# 02_ZYNQ_POWER.net
KiCad netlist of a schematic drawn in Altium Designer
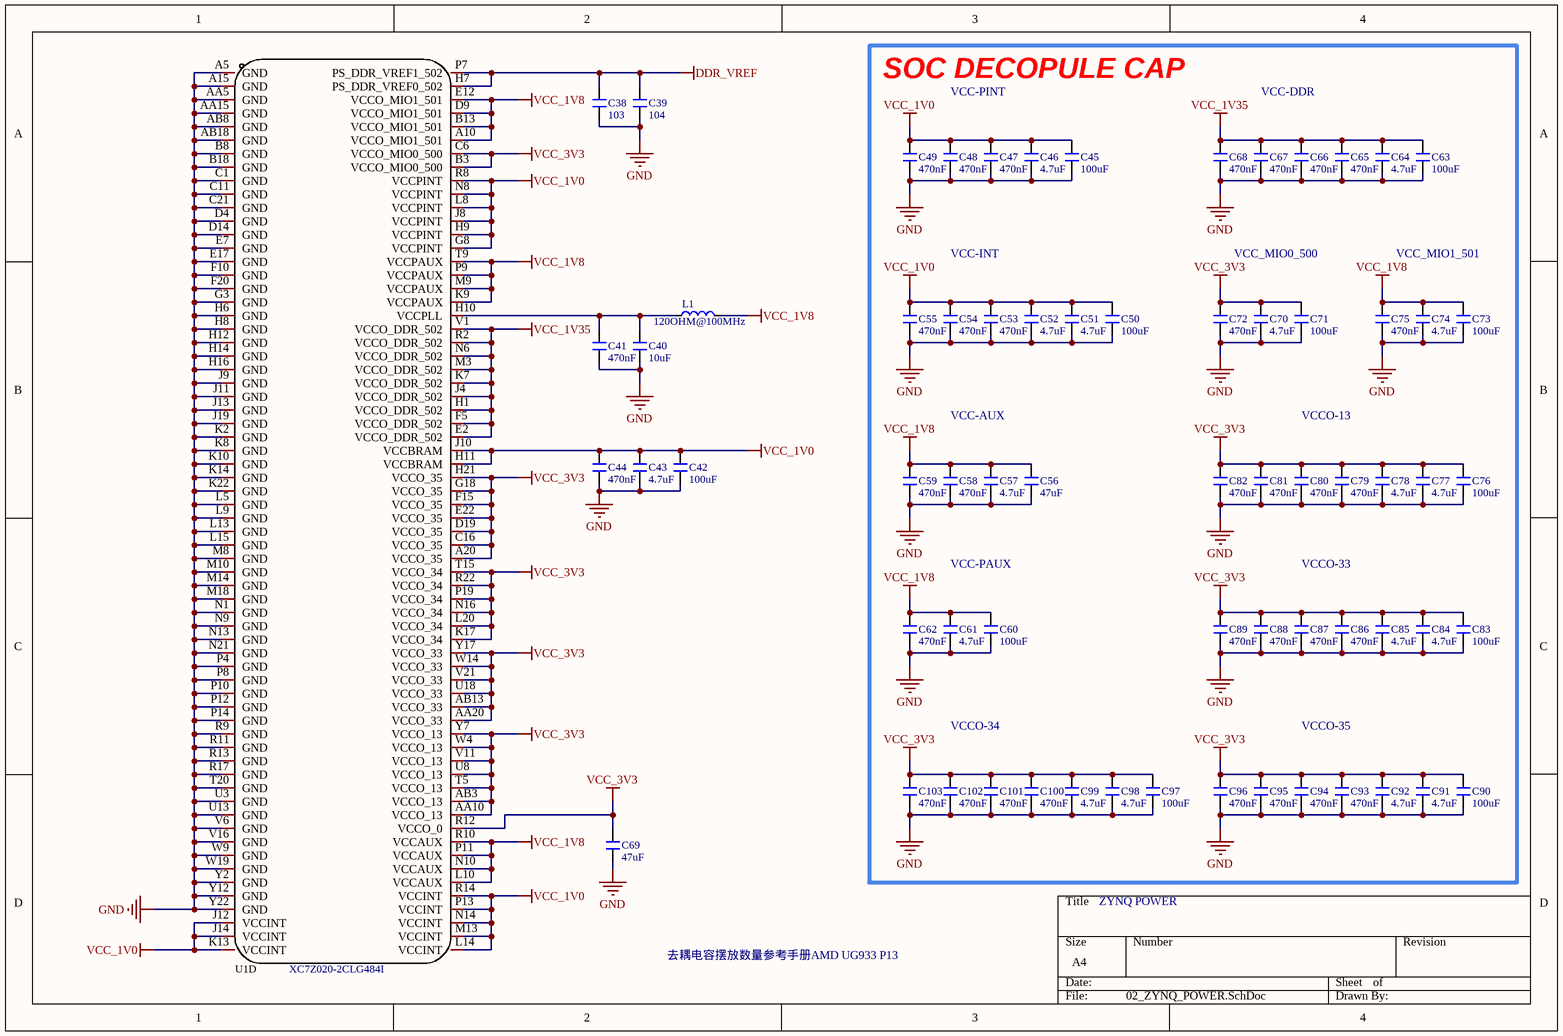
[diagram p0: 02_ZYNQ_POWER.SchDoc]

(export (version "E")
  (design (tool "Eeschema 10.0.6"))
  (components
    (comp (ref "C38")
      (value "103")
      (footprint "C 0402")
      (description "无极性贴片电容")
      (fields (field (name "版权归属") "源创客"))
      (libsource (lib "STM32MP157核心板封装库V1.2") (part "C"))
    )
    (comp (ref "C39")
      (value "104")
      (footprint "C 0402")
      (description "无极性贴片电容")
      (fields (field (name "版权归属") "源创客"))
      (libsource (lib "STM32MP157核心板封装库V1.2") (part "C"))
    )
    (comp (ref "C40")
      (value "10uF")
      (footprint "C 0402")
      (description "无极性贴片电容")
      (fields (field (name "版权归属") "源创客"))
      (libsource (lib "STM32MP157核心板封装库V1.2") (part "C"))
    )
    (comp (ref "C41")
      (value "470nF")
      (footprint "C 0402")
      (description "无极性贴片电容")
      (fields (field (name "版权归属") "源创客"))
      (libsource (lib "STM32MP157核心板封装库V1.2") (part "C"))
    )
    (comp (ref "C42")
      (value "100uF")
      (footprint "C 0805")
      (description "无极性贴片电容")
      (fields (field (name "版权归属") "源创客"))
      (libsource (lib "STM32MP157核心板封装库V1.2") (part "C"))
    )
    (comp (ref "C43")
      (value "4.7uF")
      (footprint "C 0402")
      (description "无极性贴片电容")
      (fields (field (name "版权归属") "源创客"))
      (libsource (lib "STM32MP157核心板封装库V1.2") (part "C"))
    )
    (comp (ref "C44")
      (value "470nF")
      (footprint "C 0402")
      (description "无极性贴片电容")
      (fields (field (name "版权归属") "源创客"))
      (libsource (lib "STM32MP157核心板封装库V1.2") (part "C"))
    )
    (comp (ref "C45")
      (value "100uF")
      (footprint "C 0805")
      (description "无极性贴片电容")
      (fields (field (name "版权归属") "源创客"))
      (libsource (lib "STM32MP157核心板封装库V1.2") (part "C"))
    )
    (comp (ref "C46")
      (value "4.7uF")
      (footprint "C 0402")
      (description "无极性贴片电容")
      (fields (field (name "版权归属") "源创客"))
      (libsource (lib "STM32MP157核心板封装库V1.2") (part "C"))
    )
    (comp (ref "C47")
      (value "470nF")
      (footprint "C 0402")
      (description "无极性贴片电容")
      (fields (field (name "版权归属") "源创客"))
      (libsource (lib "STM32MP157核心板封装库V1.2") (part "C"))
    )
    (comp (ref "C48")
      (value "470nF")
      (footprint "C 0402")
      (description "无极性贴片电容")
      (fields (field (name "版权归属") "源创客"))
      (libsource (lib "STM32MP157核心板封装库V1.2") (part "C"))
    )
    (comp (ref "C49")
      (value "470nF")
      (footprint "C 0402")
      (description "无极性贴片电容")
      (fields (field (name "版权归属") "源创客"))
      (libsource (lib "STM32MP157核心板封装库V1.2") (part "C"))
    )
    (comp (ref "C50")
      (value "100uF")
      (footprint "C 0805")
      (description "无极性贴片电容")
      (fields (field (name "版权归属") "源创客"))
      (libsource (lib "STM32MP157核心板封装库V1.2") (part "C"))
    )
    (comp (ref "C51")
      (value "4.7uF")
      (footprint "C 0402")
      (description "无极性贴片电容")
      (fields (field (name "版权归属") "源创客"))
      (libsource (lib "STM32MP157核心板封装库V1.2") (part "C"))
    )
    (comp (ref "C52")
      (value "4.7uF")
      (footprint "C 0402")
      (description "无极性贴片电容")
      (fields (field (name "版权归属") "源创客"))
      (libsource (lib "STM32MP157核心板封装库V1.2") (part "C"))
    )
    (comp (ref "C53")
      (value "470nF")
      (footprint "C 0402")
      (description "无极性贴片电容")
      (fields (field (name "版权归属") "源创客"))
      (libsource (lib "STM32MP157核心板封装库V1.2") (part "C"))
    )
    (comp (ref "C54")
      (value "470nF")
      (footprint "C 0402")
      (description "无极性贴片电容")
      (fields (field (name "版权归属") "源创客"))
      (libsource (lib "STM32MP157核心板封装库V1.2") (part "C"))
    )
    (comp (ref "C55")
      (value "470nF")
      (footprint "C 0402")
      (description "无极性贴片电容")
      (fields (field (name "版权归属") "源创客"))
      (libsource (lib "STM32MP157核心板封装库V1.2") (part "C"))
    )
    (comp (ref "C56")
      (value "47uF")
      (footprint "C 0805")
      (description "无极性贴片电容")
      (fields (field (name "版权归属") "源创客"))
      (libsource (lib "STM32MP157核心板封装库V1.2") (part "C"))
    )
    (comp (ref "C57")
      (value "4.7uF")
      (footprint "C 0402")
      (description "无极性贴片电容")
      (fields (field (name "版权归属") "源创客"))
      (libsource (lib "STM32MP157核心板封装库V1.2") (part "C"))
    )
    (comp (ref "C58")
      (value "470nF")
      (footprint "C 0402")
      (description "无极性贴片电容")
      (fields (field (name "版权归属") "源创客"))
      (libsource (lib "STM32MP157核心板封装库V1.2") (part "C"))
    )
    (comp (ref "C59")
      (value "470nF")
      (footprint "C 0402")
      (description "无极性贴片电容")
      (fields (field (name "版权归属") "源创客"))
      (libsource (lib "STM32MP157核心板封装库V1.2") (part "C"))
    )
    (comp (ref "C60")
      (value "100uF")
      (footprint "C 0805")
      (description "无极性贴片电容")
      (fields (field (name "版权归属") "源创客"))
      (libsource (lib "STM32MP157核心板封装库V1.2") (part "C"))
    )
    (comp (ref "C61")
      (value "4.7uF")
      (footprint "C 0402")
      (description "无极性贴片电容")
      (fields (field (name "版权归属") "源创客"))
      (libsource (lib "STM32MP157核心板封装库V1.2") (part "C"))
    )
    (comp (ref "C62")
      (value "470nF")
      (footprint "C 0402")
      (description "无极性贴片电容")
      (fields (field (name "版权归属") "源创客"))
      (libsource (lib "STM32MP157核心板封装库V1.2") (part "C"))
    )
    (comp (ref "C63")
      (value "100uF")
      (footprint "C 0805")
      (description "无极性贴片电容")
      (fields (field (name "版权归属") "源创客"))
      (libsource (lib "STM32MP157核心板封装库V1.2") (part "C"))
    )
    (comp (ref "C64")
      (value "4.7uF")
      (footprint "C 0402")
      (description "无极性贴片电容")
      (fields (field (name "版权归属") "源创客"))
      (libsource (lib "STM32MP157核心板封装库V1.2") (part "C"))
    )
    (comp (ref "C65")
      (value "470nF")
      (footprint "C 0402")
      (description "无极性贴片电容")
      (fields (field (name "版权归属") "源创客"))
      (libsource (lib "STM32MP157核心板封装库V1.2") (part "C"))
    )
    (comp (ref "C66")
      (value "470nF")
      (footprint "C 0402")
      (description "无极性贴片电容")
      (fields (field (name "版权归属") "源创客"))
      (libsource (lib "STM32MP157核心板封装库V1.2") (part "C"))
    )
    (comp (ref "C67")
      (value "470nF")
      (footprint "C 0402")
      (description "无极性贴片电容")
      (fields (field (name "版权归属") "源创客"))
      (libsource (lib "STM32MP157核心板封装库V1.2") (part "C"))
    )
    (comp (ref "C68")
      (value "470nF")
      (footprint "C 0402")
      (description "无极性贴片电容")
      (fields (field (name "版权归属") "源创客"))
      (libsource (lib "STM32MP157核心板封装库V1.2") (part "C"))
    )
    (comp (ref "C69")
      (value "47uF")
      (footprint "C 0805")
      (description "无极性贴片电容")
      (fields (field (name "版权归属") "源创客"))
      (libsource (lib "STM32MP157核心板封装库V1.2") (part "C"))
    )
    (comp (ref "C70")
      (value "4.7uF")
      (footprint "C 0402")
      (description "无极性贴片电容")
      (fields (field (name "版权归属") "源创客"))
      (libsource (lib "STM32MP157核心板封装库V1.2") (part "C"))
    )
    (comp (ref "C71")
      (value "100uF")
      (footprint "C 0805")
      (description "无极性贴片电容")
      (fields (field (name "版权归属") "源创客"))
      (libsource (lib "STM32MP157核心板封装库V1.2") (part "C"))
    )
    (comp (ref "C72")
      (value "470nF")
      (footprint "C 0402")
      (description "无极性贴片电容")
      (fields (field (name "版权归属") "源创客"))
      (libsource (lib "STM32MP157核心板封装库V1.2") (part "C"))
    )
    (comp (ref "C73")
      (value "100uF")
      (footprint "C 0805")
      (description "无极性贴片电容")
      (fields (field (name "版权归属") "源创客"))
      (libsource (lib "STM32MP157核心板封装库V1.2") (part "C"))
    )
    (comp (ref "C74")
      (value "4.7uF")
      (footprint "C 0402")
      (description "无极性贴片电容")
      (fields (field (name "版权归属") "源创客"))
      (libsource (lib "STM32MP157核心板封装库V1.2") (part "C"))
    )
    (comp (ref "C75")
      (value "470nF")
      (footprint "C 0402")
      (description "无极性贴片电容")
      (fields (field (name "版权归属") "源创客"))
      (libsource (lib "STM32MP157核心板封装库V1.2") (part "C"))
    )
    (comp (ref "C76")
      (value "100uF")
      (footprint "C 0805")
      (description "无极性贴片电容")
      (fields (field (name "版权归属") "源创客"))
      (libsource (lib "STM32MP157核心板封装库V1.2") (part "C"))
    )
    (comp (ref "C77")
      (value "4.7uF")
      (footprint "C 0402")
      (description "无极性贴片电容")
      (fields (field (name "版权归属") "源创客"))
      (libsource (lib "STM32MP157核心板封装库V1.2") (part "C"))
    )
    (comp (ref "C78")
      (value "4.7uF")
      (footprint "C 0402")
      (description "无极性贴片电容")
      (fields (field (name "版权归属") "源创客"))
      (libsource (lib "STM32MP157核心板封装库V1.2") (part "C"))
    )
    (comp (ref "C79")
      (value "470nF")
      (footprint "C 0402")
      (description "无极性贴片电容")
      (fields (field (name "版权归属") "源创客"))
      (libsource (lib "STM32MP157核心板封装库V1.2") (part "C"))
    )
    (comp (ref "C80")
      (value "470nF")
      (footprint "C 0402")
      (description "无极性贴片电容")
      (fields (field (name "版权归属") "源创客"))
      (libsource (lib "STM32MP157核心板封装库V1.2") (part "C"))
    )
    (comp (ref "C81")
      (value "470nF")
      (footprint "C 0402")
      (description "无极性贴片电容")
      (fields (field (name "版权归属") "源创客"))
      (libsource (lib "STM32MP157核心板封装库V1.2") (part "C"))
    )
    (comp (ref "C82")
      (value "470nF")
      (footprint "C 0402")
      (description "无极性贴片电容")
      (fields (field (name "版权归属") "源创客"))
      (libsource (lib "STM32MP157核心板封装库V1.2") (part "C"))
    )
    (comp (ref "C83")
      (value "100uF")
      (footprint "C 0805")
      (description "无极性贴片电容")
      (fields (field (name "版权归属") "源创客"))
      (libsource (lib "STM32MP157核心板封装库V1.2") (part "C"))
    )
    (comp (ref "C84")
      (value "4.7uF")
      (footprint "C 0402")
      (description "无极性贴片电容")
      (fields (field (name "版权归属") "源创客"))
      (libsource (lib "STM32MP157核心板封装库V1.2") (part "C"))
    )
    (comp (ref "C85")
      (value "4.7uF")
      (footprint "C 0402")
      (description "无极性贴片电容")
      (fields (field (name "版权归属") "源创客"))
      (libsource (lib "STM32MP157核心板封装库V1.2") (part "C"))
    )
    (comp (ref "C86")
      (value "470nF")
      (footprint "C 0402")
      (description "无极性贴片电容")
      (fields (field (name "版权归属") "源创客"))
      (libsource (lib "STM32MP157核心板封装库V1.2") (part "C"))
    )
    (comp (ref "C87")
      (value "470nF")
      (footprint "C 0402")
      (description "无极性贴片电容")
      (fields (field (name "版权归属") "源创客"))
      (libsource (lib "STM32MP157核心板封装库V1.2") (part "C"))
    )
    (comp (ref "C88")
      (value "470nF")
      (footprint "C 0402")
      (description "无极性贴片电容")
      (fields (field (name "版权归属") "源创客"))
      (libsource (lib "STM32MP157核心板封装库V1.2") (part "C"))
    )
    (comp (ref "C89")
      (value "470nF")
      (footprint "C 0402")
      (description "无极性贴片电容")
      (fields (field (name "版权归属") "源创客"))
      (libsource (lib "STM32MP157核心板封装库V1.2") (part "C"))
    )
    (comp (ref "C90")
      (value "100uF")
      (footprint "C 0805")
      (description "无极性贴片电容")
      (fields (field (name "版权归属") "源创客"))
      (libsource (lib "STM32MP157核心板封装库V1.2") (part "C"))
    )
    (comp (ref "C91")
      (value "4.7uF")
      (footprint "C 0402")
      (description "无极性贴片电容")
      (fields (field (name "版权归属") "源创客"))
      (libsource (lib "STM32MP157核心板封装库V1.2") (part "C"))
    )
    (comp (ref "C92")
      (value "4.7uF")
      (footprint "C 0402")
      (description "无极性贴片电容")
      (fields (field (name "版权归属") "源创客"))
      (libsource (lib "STM32MP157核心板封装库V1.2") (part "C"))
    )
    (comp (ref "C93")
      (value "470nF")
      (footprint "C 0402")
      (description "无极性贴片电容")
      (fields (field (name "版权归属") "源创客"))
      (libsource (lib "STM32MP157核心板封装库V1.2") (part "C"))
    )
    (comp (ref "C94")
      (value "470nF")
      (footprint "C 0402")
      (description "无极性贴片电容")
      (fields (field (name "版权归属") "源创客"))
      (libsource (lib "STM32MP157核心板封装库V1.2") (part "C"))
    )
    (comp (ref "C95")
      (value "470nF")
      (footprint "C 0402")
      (description "无极性贴片电容")
      (fields (field (name "版权归属") "源创客"))
      (libsource (lib "STM32MP157核心板封装库V1.2") (part "C"))
    )
    (comp (ref "C96")
      (value "470nF")
      (footprint "C 0402")
      (description "无极性贴片电容")
      (fields (field (name "版权归属") "源创客"))
      (libsource (lib "STM32MP157核心板封装库V1.2") (part "C"))
    )
    (comp (ref "C97")
      (value "100uF")
      (footprint "C 0805")
      (description "无极性贴片电容")
      (fields (field (name "版权归属") "源创客"))
      (libsource (lib "STM32MP157核心板封装库V1.2") (part "C"))
    )
    (comp (ref "C98")
      (value "4.7uF")
      (footprint "C 0402")
      (description "无极性贴片电容")
      (fields (field (name "版权归属") "源创客"))
      (libsource (lib "STM32MP157核心板封装库V1.2") (part "C"))
    )
    (comp (ref "C99")
      (value "4.7uF")
      (footprint "C 0402")
      (description "无极性贴片电容")
      (fields (field (name "版权归属") "源创客"))
      (libsource (lib "STM32MP157核心板封装库V1.2") (part "C"))
    )
    (comp (ref "C100")
      (value "470nF")
      (footprint "C 0402")
      (description "无极性贴片电容")
      (fields (field (name "版权归属") "源创客"))
      (libsource (lib "STM32MP157核心板封装库V1.2") (part "C"))
    )
    (comp (ref "C101")
      (value "470nF")
      (footprint "C 0402")
      (description "无极性贴片电容")
      (fields (field (name "版权归属") "源创客"))
      (libsource (lib "STM32MP157核心板封装库V1.2") (part "C"))
    )
    (comp (ref "C102")
      (value "470nF")
      (footprint "C 0402")
      (description "无极性贴片电容")
      (fields (field (name "版权归属") "源创客"))
      (libsource (lib "STM32MP157核心板封装库V1.2") (part "C"))
    )
    (comp (ref "C103")
      (value "470nF")
      (footprint "C 0402")
      (description "无极性贴片电容")
      (fields (field (name "版权归属") "源创客"))
      (libsource (lib "STM32MP157核心板封装库V1.2") (part "C"))
    )
    (comp (ref "L1")
      (value "120OHM@100MHz")
      (footprint "L 0603")
      (description "小功率贴片电感磁珠")
      (fields (field (name "版权归属") "源创客"))
      (libsource (lib "STM32MP157核心板封装库V1.2") (part "L"))
    )
    (comp (ref "U1")
      (value "XC7Z020-2CLG484I")
      (footprint "FPBGA-484_L19.0-W19.0-R22-C22-P0.80-BL")
      (fields (field (name "MANUFACTURER") "XILINX(赛灵思)"))
      (libsource (lib "XC7Z020-2CLG484I1") (part "XC7Z020-2CLG484I"))
    )
  )
  (nets
    (net (code "1") (name "DDR_VREF") (class "Default")
      (node (ref "C38") (pin "2") (pinfunction "2_2") (pintype "passive"))
      (node (ref "C39") (pin "2") (pinfunction "2_2") (pintype "passive"))
      (node (ref "U1") (pin "H7") (pinfunction "PS_DDR_VREF0_502_H7") (pintype "passive"))
      (node (ref "U1") (pin "P7") (pinfunction "PS_DDR_VREF1_502_P7") (pintype "passive"))
    )
    (net (code "2") (name "GND") (class "Default")
      (node (ref "C100") (pin "1") (pinfunction "1_1") (pintype "passive"))
      (node (ref "C101") (pin "1") (pinfunction "1_1") (pintype "passive"))
      (node (ref "C102") (pin "1") (pinfunction "1_1") (pintype "passive"))
      (node (ref "C103") (pin "1") (pinfunction "1_1") (pintype "passive"))
      (node (ref "C38") (pin "1") (pinfunction "1_1") (pintype "passive"))
      (node (ref "C39") (pin "1") (pinfunction "1_1") (pintype "passive"))
      (node (ref "C40") (pin "1") (pinfunction "1_1") (pintype "passive"))
      (node (ref "C41") (pin "1") (pinfunction "1_1") (pintype "passive"))
      (node (ref "C42") (pin "1") (pinfunction "1_1") (pintype "passive"))
      (node (ref "C43") (pin "1") (pinfunction "1_1") (pintype "passive"))
      (node (ref "C44") (pin "1") (pinfunction "1_1") (pintype "passive"))
      (node (ref "C45") (pin "1") (pinfunction "1_1") (pintype "passive"))
      (node (ref "C46") (pin "1") (pinfunction "1_1") (pintype "passive"))
      (node (ref "C47") (pin "1") (pinfunction "1_1") (pintype "passive"))
      (node (ref "C48") (pin "1") (pinfunction "1_1") (pintype "passive"))
      (node (ref "C49") (pin "1") (pinfunction "1_1") (pintype "passive"))
      (node (ref "C50") (pin "1") (pinfunction "1_1") (pintype "passive"))
      (node (ref "C51") (pin "1") (pinfunction "1_1") (pintype "passive"))
      (node (ref "C52") (pin "1") (pinfunction "1_1") (pintype "passive"))
      (node (ref "C53") (pin "1") (pinfunction "1_1") (pintype "passive"))
      (node (ref "C54") (pin "1") (pinfunction "1_1") (pintype "passive"))
      (node (ref "C55") (pin "1") (pinfunction "1_1") (pintype "passive"))
      (node (ref "C56") (pin "1") (pinfunction "1_1") (pintype "passive"))
      (node (ref "C57") (pin "1") (pinfunction "1_1") (pintype "passive"))
      (node (ref "C58") (pin "1") (pinfunction "1_1") (pintype "passive"))
      (node (ref "C59") (pin "1") (pinfunction "1_1") (pintype "passive"))
      (node (ref "C60") (pin "1") (pinfunction "1_1") (pintype "passive"))
      (node (ref "C61") (pin "1") (pinfunction "1_1") (pintype "passive"))
      (node (ref "C62") (pin "1") (pinfunction "1_1") (pintype "passive"))
      (node (ref "C63") (pin "1") (pinfunction "1_1") (pintype "passive"))
      (node (ref "C64") (pin "1") (pinfunction "1_1") (pintype "passive"))
      (node (ref "C65") (pin "1") (pinfunction "1_1") (pintype "passive"))
      (node (ref "C66") (pin "1") (pinfunction "1_1") (pintype "passive"))
      (node (ref "C67") (pin "1") (pinfunction "1_1") (pintype "passive"))
      (node (ref "C68") (pin "1") (pinfunction "1_1") (pintype "passive"))
      (node (ref "C69") (pin "1") (pinfunction "1_1") (pintype "passive"))
      (node (ref "C70") (pin "1") (pinfunction "1_1") (pintype "passive"))
      (node (ref "C71") (pin "1") (pinfunction "1_1") (pintype "passive"))
      (node (ref "C72") (pin "1") (pinfunction "1_1") (pintype "passive"))
      (node (ref "C73") (pin "1") (pinfunction "1_1") (pintype "passive"))
      (node (ref "C74") (pin "1") (pinfunction "1_1") (pintype "passive"))
      (node (ref "C75") (pin "1") (pinfunction "1_1") (pintype "passive"))
      (node (ref "C76") (pin "1") (pinfunction "1_1") (pintype "passive"))
      (node (ref "C77") (pin "1") (pinfunction "1_1") (pintype "passive"))
      (node (ref "C78") (pin "1") (pinfunction "1_1") (pintype "passive"))
      (node (ref "C79") (pin "1") (pinfunction "1_1") (pintype "passive"))
      (node (ref "C80") (pin "1") (pinfunction "1_1") (pintype "passive"))
      (node (ref "C81") (pin "1") (pinfunction "1_1") (pintype "passive"))
      (node (ref "C82") (pin "1") (pinfunction "1_1") (pintype "passive"))
      (node (ref "C83") (pin "1") (pinfunction "1_1") (pintype "passive"))
      (node (ref "C84") (pin "1") (pinfunction "1_1") (pintype "passive"))
      (node (ref "C85") (pin "1") (pinfunction "1_1") (pintype "passive"))
      (node (ref "C86") (pin "1") (pinfunction "1_1") (pintype "passive"))
      (node (ref "C87") (pin "1") (pinfunction "1_1") (pintype "passive"))
      (node (ref "C88") (pin "1") (pinfunction "1_1") (pintype "passive"))
      (node (ref "C89") (pin "1") (pinfunction "1_1") (pintype "passive"))
      (node (ref "C90") (pin "1") (pinfunction "1_1") (pintype "passive"))
      (node (ref "C91") (pin "1") (pinfunction "1_1") (pintype "passive"))
      (node (ref "C92") (pin "1") (pinfunction "1_1") (pintype "passive"))
      (node (ref "C93") (pin "1") (pinfunction "1_1") (pintype "passive"))
      (node (ref "C94") (pin "1") (pinfunction "1_1") (pintype "passive"))
      (node (ref "C95") (pin "1") (pinfunction "1_1") (pintype "passive"))
      (node (ref "C96") (pin "1") (pinfunction "1_1") (pintype "passive"))
      (node (ref "C97") (pin "1") (pinfunction "1_1") (pintype "passive"))
      (node (ref "C98") (pin "1") (pinfunction "1_1") (pintype "passive"))
      (node (ref "C99") (pin "1") (pinfunction "1_1") (pintype "passive"))
      (node (ref "U1") (pin "A15") (pinfunction "GND_A15") (pintype "passive"))
      (node (ref "U1") (pin "A5") (pinfunction "GND_A5") (pintype "passive"))
      (node (ref "U1") (pin "AA15") (pinfunction "GND_AA15") (pintype "passive"))
      (node (ref "U1") (pin "AA5") (pinfunction "GND_AA5") (pintype "passive"))
      (node (ref "U1") (pin "AB18") (pinfunction "GND_AB18") (pintype "passive"))
      (node (ref "U1") (pin "AB8") (pinfunction "GND_AB8") (pintype "passive"))
      (node (ref "U1") (pin "B18") (pinfunction "GND_B18") (pintype "passive"))
      (node (ref "U1") (pin "B8") (pinfunction "GND_B8") (pintype "passive"))
      (node (ref "U1") (pin "C1") (pinfunction "GND_C1") (pintype "passive"))
      (node (ref "U1") (pin "C11") (pinfunction "GND_C11") (pintype "passive"))
      (node (ref "U1") (pin "C21") (pinfunction "GND_C21") (pintype "passive"))
      (node (ref "U1") (pin "D14") (pinfunction "GND_D14") (pintype "passive"))
      (node (ref "U1") (pin "D4") (pinfunction "GND_D4") (pintype "passive"))
      (node (ref "U1") (pin "E17") (pinfunction "GND_E17") (pintype "passive"))
      (node (ref "U1") (pin "E7") (pinfunction "GND_E7") (pintype "passive"))
      (node (ref "U1") (pin "F10") (pinfunction "GND_F10") (pintype "passive"))
      (node (ref "U1") (pin "F20") (pinfunction "GND_F20") (pintype "passive"))
      (node (ref "U1") (pin "G3") (pinfunction "GND_G3") (pintype "passive"))
      (node (ref "U1") (pin "H12") (pinfunction "GND_H12") (pintype "passive"))
      (node (ref "U1") (pin "H14") (pinfunction "GND_H14") (pintype "passive"))
      (node (ref "U1") (pin "H16") (pinfunction "GND_H16") (pintype "passive"))
      (node (ref "U1") (pin "H6") (pinfunction "GND_H6") (pintype "passive"))
      (node (ref "U1") (pin "H8") (pinfunction "GND_H8") (pintype "passive"))
      (node (ref "U1") (pin "J11") (pinfunction "GND_J11") (pintype "passive"))
      (node (ref "U1") (pin "J13") (pinfunction "GND_J13") (pintype "passive"))
      (node (ref "U1") (pin "J19") (pinfunction "GND_J19") (pintype "passive"))
      (node (ref "U1") (pin "J9") (pinfunction "GND_J9") (pintype "passive"))
      (node (ref "U1") (pin "K10") (pinfunction "GND_K10") (pintype "passive"))
      (node (ref "U1") (pin "K14") (pinfunction "GND_K14") (pintype "passive"))
      (node (ref "U1") (pin "K2") (pinfunction "GND_K2") (pintype "passive"))
      (node (ref "U1") (pin "K22") (pinfunction "GND_K22") (pintype "passive"))
      (node (ref "U1") (pin "K8") (pinfunction "GND_K8") (pintype "passive"))
      (node (ref "U1") (pin "L13") (pinfunction "GND_L13") (pintype "passive"))
      (node (ref "U1") (pin "L15") (pinfunction "GND_L15") (pintype "passive"))
      (node (ref "U1") (pin "L5") (pinfunction "GND_L5") (pintype "passive"))
      (node (ref "U1") (pin "L9") (pinfunction "GND_L9") (pintype "passive"))
      (node (ref "U1") (pin "M10") (pinfunction "GND_M10") (pintype "passive"))
      (node (ref "U1") (pin "M14") (pinfunction "GND_M14") (pintype "passive"))
      (node (ref "U1") (pin "M18") (pinfunction "GND_M18") (pintype "passive"))
      (node (ref "U1") (pin "M8") (pinfunction "GND_M8") (pintype "passive"))
      (node (ref "U1") (pin "N1") (pinfunction "GND_N1") (pintype "passive"))
      (node (ref "U1") (pin "N13") (pinfunction "GND_N13") (pintype "passive"))
      (node (ref "U1") (pin "N21") (pinfunction "GND_N21") (pintype "passive"))
      (node (ref "U1") (pin "N9") (pinfunction "GND_N9") (pintype "passive"))
      (node (ref "U1") (pin "P10") (pinfunction "GND_P10") (pintype "passive"))
      (node (ref "U1") (pin "P12") (pinfunction "GND_P12") (pintype "passive"))
      (node (ref "U1") (pin "P14") (pinfunction "GND_P14") (pintype "passive"))
      (node (ref "U1") (pin "P4") (pinfunction "GND_P4") (pintype "passive"))
      (node (ref "U1") (pin "P8") (pinfunction "GND_P8") (pintype "passive"))
      (node (ref "U1") (pin "R11") (pinfunction "GND_R11") (pintype "passive"))
      (node (ref "U1") (pin "R13") (pinfunction "GND_R13") (pintype "passive"))
      (node (ref "U1") (pin "R17") (pinfunction "GND_R17") (pintype "passive"))
      (node (ref "U1") (pin "R9") (pinfunction "GND_R9") (pintype "passive"))
      (node (ref "U1") (pin "T20") (pinfunction "GND_T20") (pintype "passive"))
      (node (ref "U1") (pin "U13") (pinfunction "GND_U13") (pintype "passive"))
      (node (ref "U1") (pin "U3") (pinfunction "GND_U3") (pintype "passive"))
      (node (ref "U1") (pin "V16") (pinfunction "GND_V16") (pintype "passive"))
      (node (ref "U1") (pin "V6") (pinfunction "GND_V6") (pintype "passive"))
      (node (ref "U1") (pin "W19") (pinfunction "GND_W19") (pintype "passive"))
      (node (ref "U1") (pin "W9") (pinfunction "GND_W9") (pintype "passive"))
      (node (ref "U1") (pin "Y12") (pinfunction "GND_Y12") (pintype "passive"))
      (node (ref "U1") (pin "Y2") (pinfunction "GND_Y2") (pintype "passive"))
      (node (ref "U1") (pin "Y22") (pinfunction "GND_Y22") (pintype "passive"))
    )
    (net (code "3") (name "Net-(U1D-VCCPLL)") (class "Default")
      (node (ref "C40") (pin "2") (pinfunction "2_2") (pintype "passive"))
      (node (ref "C41") (pin "2") (pinfunction "2_2") (pintype "passive"))
      (node (ref "L1") (pin "1") (pinfunction "1_1") (pintype "passive"))
      (node (ref "U1") (pin "H10") (pinfunction "VCCPLL_H10") (pintype "passive"))
    )
    (net (code "4") (name "VCC_1V0") (class "Default")
      (node (ref "C42") (pin "2") (pinfunction "2_2") (pintype "passive"))
      (node (ref "C43") (pin "2") (pinfunction "2_2") (pintype "passive"))
      (node (ref "C44") (pin "2") (pinfunction "2_2") (pintype "passive"))
      (node (ref "C45") (pin "2") (pinfunction "2_2") (pintype "passive"))
      (node (ref "C46") (pin "2") (pinfunction "2_2") (pintype "passive"))
      (node (ref "C47") (pin "2") (pinfunction "2_2") (pintype "passive"))
      (node (ref "C48") (pin "2") (pinfunction "2_2") (pintype "passive"))
      (node (ref "C49") (pin "2") (pinfunction "2_2") (pintype "passive"))
      (node (ref "C50") (pin "2") (pinfunction "2_2") (pintype "passive"))
      (node (ref "C51") (pin "2") (pinfunction "2_2") (pintype "passive"))
      (node (ref "C52") (pin "2") (pinfunction "2_2") (pintype "passive"))
      (node (ref "C53") (pin "2") (pinfunction "2_2") (pintype "passive"))
      (node (ref "C54") (pin "2") (pinfunction "2_2") (pintype "passive"))
      (node (ref "C55") (pin "2") (pinfunction "2_2") (pintype "passive"))
      (node (ref "U1") (pin "G8") (pinfunction "VCCPINT_G8") (pintype "passive"))
      (node (ref "U1") (pin "H11") (pinfunction "VCCBRAM_H11") (pintype "passive"))
      (node (ref "U1") (pin "H9") (pinfunction "VCCPINT_H9") (pintype "passive"))
      (node (ref "U1") (pin "J10") (pinfunction "VCCBRAM_J10") (pintype "passive"))
      (node (ref "U1") (pin "J12") (pinfunction "VCCINT_J12") (pintype "passive"))
      (node (ref "U1") (pin "J14") (pinfunction "VCCINT_J14") (pintype "passive"))
      (node (ref "U1") (pin "J8") (pinfunction "VCCPINT_J8") (pintype "passive"))
      (node (ref "U1") (pin "K13") (pinfunction "VCCINT_K13") (pintype "passive"))
      (node (ref "U1") (pin "L14") (pinfunction "VCCINT_L14") (pintype "passive"))
      (node (ref "U1") (pin "L8") (pinfunction "VCCPINT_L8") (pintype "passive"))
      (node (ref "U1") (pin "M13") (pinfunction "VCCINT_M13") (pintype "passive"))
      (node (ref "U1") (pin "N14") (pinfunction "VCCINT_N14") (pintype "passive"))
      (node (ref "U1") (pin "N8") (pinfunction "VCCPINT_N8") (pintype "passive"))
      (node (ref "U1") (pin "P13") (pinfunction "VCCINT_P13") (pintype "passive"))
      (node (ref "U1") (pin "R14") (pinfunction "VCCINT_R14") (pintype "passive"))
      (node (ref "U1") (pin "R8") (pinfunction "VCCPINT_R8") (pintype "passive"))
    )
    (net (code "5") (name "VCC_1V8") (class "Default")
      (node (ref "C56") (pin "2") (pinfunction "2_2") (pintype "passive"))
      (node (ref "C57") (pin "2") (pinfunction "2_2") (pintype "passive"))
      (node (ref "C58") (pin "2") (pinfunction "2_2") (pintype "passive"))
      (node (ref "C59") (pin "2") (pinfunction "2_2") (pintype "passive"))
      (node (ref "C60") (pin "2") (pinfunction "2_2") (pintype "passive"))
      (node (ref "C61") (pin "2") (pinfunction "2_2") (pintype "passive"))
      (node (ref "C62") (pin "2") (pinfunction "2_2") (pintype "passive"))
      (node (ref "C73") (pin "2") (pinfunction "2_2") (pintype "passive"))
      (node (ref "C74") (pin "2") (pinfunction "2_2") (pintype "passive"))
      (node (ref "C75") (pin "2") (pinfunction "2_2") (pintype "passive"))
      (node (ref "L1") (pin "2") (pinfunction "2_2") (pintype "passive"))
      (node (ref "U1") (pin "A10") (pinfunction "VCCO_MIO1_501_A10") (pintype "passive"))
      (node (ref "U1") (pin "B13") (pinfunction "VCCO_MIO1_501_B13") (pintype "passive"))
      (node (ref "U1") (pin "D9") (pinfunction "VCCO_MIO1_501_D9") (pintype "passive"))
      (node (ref "U1") (pin "E12") (pinfunction "VCCO_MIO1_501_E12") (pintype "passive"))
      (node (ref "U1") (pin "K9") (pinfunction "VCCPAUX_K9") (pintype "passive"))
      (node (ref "U1") (pin "L10") (pinfunction "VCCAUX_L10") (pintype "passive"))
      (node (ref "U1") (pin "M9") (pinfunction "VCCPAUX_M9") (pintype "passive"))
      (node (ref "U1") (pin "N10") (pinfunction "VCCAUX_N10") (pintype "passive"))
      (node (ref "U1") (pin "P11") (pinfunction "VCCAUX_P11") (pintype "passive"))
      (node (ref "U1") (pin "P9") (pinfunction "VCCPAUX_P9") (pintype "passive"))
      (node (ref "U1") (pin "R10") (pinfunction "VCCAUX_R10") (pintype "passive"))
      (node (ref "U1") (pin "T9") (pinfunction "VCCPAUX_T9") (pintype "passive"))
    )
    (net (code "6") (name "VCC_1V35") (class "Default")
      (node (ref "C63") (pin "2") (pinfunction "2_2") (pintype "passive"))
      (node (ref "C64") (pin "2") (pinfunction "2_2") (pintype "passive"))
      (node (ref "C65") (pin "2") (pinfunction "2_2") (pintype "passive"))
      (node (ref "C66") (pin "2") (pinfunction "2_2") (pintype "passive"))
      (node (ref "C67") (pin "2") (pinfunction "2_2") (pintype "passive"))
      (node (ref "C68") (pin "2") (pinfunction "2_2") (pintype "passive"))
      (node (ref "U1") (pin "E2") (pinfunction "VCCO_DDR_502_E2") (pintype "passive"))
      (node (ref "U1") (pin "F5") (pinfunction "VCCO_DDR_502_F5") (pintype "passive"))
      (node (ref "U1") (pin "H1") (pinfunction "VCCO_DDR_502_H1") (pintype "passive"))
      (node (ref "U1") (pin "J4") (pinfunction "VCCO_DDR_502_J4") (pintype "passive"))
      (node (ref "U1") (pin "K7") (pinfunction "VCCO_DDR_502_K7") (pintype "passive"))
      (node (ref "U1") (pin "M3") (pinfunction "VCCO_DDR_502_M3") (pintype "passive"))
      (node (ref "U1") (pin "N6") (pinfunction "VCCO_DDR_502_N6") (pintype "passive"))
      (node (ref "U1") (pin "R2") (pinfunction "VCCO_DDR_502_R2") (pintype "passive"))
      (node (ref "U1") (pin "V1") (pinfunction "VCCO_DDR_502_V1") (pintype "passive"))
    )
    (net (code "7") (name "VCC_3V3") (class "Default")
      (node (ref "C100") (pin "2") (pinfunction "2_2") (pintype "passive"))
      (node (ref "C101") (pin "2") (pinfunction "2_2") (pintype "passive"))
      (node (ref "C102") (pin "2") (pinfunction "2_2") (pintype "passive"))
      (node (ref "C103") (pin "2") (pinfunction "2_2") (pintype "passive"))
      (node (ref "C69") (pin "2") (pinfunction "2_2") (pintype "passive"))
      (node (ref "C70") (pin "2") (pinfunction "2_2") (pintype "passive"))
      (node (ref "C71") (pin "2") (pinfunction "2_2") (pintype "passive"))
      (node (ref "C72") (pin "2") (pinfunction "2_2") (pintype "passive"))
      (node (ref "C76") (pin "2") (pinfunction "2_2") (pintype "passive"))
      (node (ref "C77") (pin "2") (pinfunction "2_2") (pintype "passive"))
      (node (ref "C78") (pin "2") (pinfunction "2_2") (pintype "passive"))
      (node (ref "C79") (pin "2") (pinfunction "2_2") (pintype "passive"))
      (node (ref "C80") (pin "2") (pinfunction "2_2") (pintype "passive"))
      (node (ref "C81") (pin "2") (pinfunction "2_2") (pintype "passive"))
      (node (ref "C82") (pin "2") (pinfunction "2_2") (pintype "passive"))
      (node (ref "C83") (pin "2") (pinfunction "2_2") (pintype "passive"))
      (node (ref "C84") (pin "2") (pinfunction "2_2") (pintype "passive"))
      (node (ref "C85") (pin "2") (pinfunction "2_2") (pintype "passive"))
      (node (ref "C86") (pin "2") (pinfunction "2_2") (pintype "passive"))
      (node (ref "C87") (pin "2") (pinfunction "2_2") (pintype "passive"))
      (node (ref "C88") (pin "2") (pinfunction "2_2") (pintype "passive"))
      (node (ref "C89") (pin "2") (pinfunction "2_2") (pintype "passive"))
      (node (ref "C90") (pin "2") (pinfunction "2_2") (pintype "passive"))
      (node (ref "C91") (pin "2") (pinfunction "2_2") (pintype "passive"))
      (node (ref "C92") (pin "2") (pinfunction "2_2") (pintype "passive"))
      (node (ref "C93") (pin "2") (pinfunction "2_2") (pintype "passive"))
      (node (ref "C94") (pin "2") (pinfunction "2_2") (pintype "passive"))
      (node (ref "C95") (pin "2") (pinfunction "2_2") (pintype "passive"))
      (node (ref "C96") (pin "2") (pinfunction "2_2") (pintype "passive"))
      (node (ref "C97") (pin "2") (pinfunction "2_2") (pintype "passive"))
      (node (ref "C98") (pin "2") (pinfunction "2_2") (pintype "passive"))
      (node (ref "C99") (pin "2") (pinfunction "2_2") (pintype "passive"))
      (node (ref "U1") (pin "A20") (pinfunction "VCCO_35_A20") (pintype "passive"))
      (node (ref "U1") (pin "AA10") (pinfunction "VCCO_13_AA10") (pintype "passive"))
      (node (ref "U1") (pin "AA20") (pinfunction "VCCO_33_AA20") (pintype "passive"))
      (node (ref "U1") (pin "AB13") (pinfunction "VCCO_33_AB13") (pintype "passive"))
      (node (ref "U1") (pin "AB3") (pinfunction "VCCO_13_AB3") (pintype "passive"))
      (node (ref "U1") (pin "B3") (pinfunction "VCCO_MIO0_500_B3") (pintype "passive"))
      (node (ref "U1") (pin "C16") (pinfunction "VCCO_35_C16") (pintype "passive"))
      (node (ref "U1") (pin "C6") (pinfunction "VCCO_MIO0_500_C6") (pintype "passive"))
      (node (ref "U1") (pin "D19") (pinfunction "VCCO_35_D19") (pintype "passive"))
      (node (ref "U1") (pin "E22") (pinfunction "VCCO_35_E22") (pintype "passive"))
      (node (ref "U1") (pin "F15") (pinfunction "VCCO_35_F15") (pintype "passive"))
      (node (ref "U1") (pin "G18") (pinfunction "VCCO_35_G18") (pintype "passive"))
      (node (ref "U1") (pin "H21") (pinfunction "VCCO_35_H21") (pintype "passive"))
      (node (ref "U1") (pin "K17") (pinfunction "VCCO_34_K17") (pintype "passive"))
      (node (ref "U1") (pin "L20") (pinfunction "VCCO_34_L20") (pintype "passive"))
      (node (ref "U1") (pin "N16") (pinfunction "VCCO_34_N16") (pintype "passive"))
      (node (ref "U1") (pin "P19") (pinfunction "VCCO_34_P19") (pintype "passive"))
      (node (ref "U1") (pin "R12") (pinfunction "VCCO_0_R12") (pintype "passive"))
      (node (ref "U1") (pin "R22") (pinfunction "VCCO_34_R22") (pintype "passive"))
      (node (ref "U1") (pin "T15") (pinfunction "VCCO_34_T15") (pintype "passive"))
      (node (ref "U1") (pin "T5") (pinfunction "VCCO_13_T5") (pintype "passive"))
      (node (ref "U1") (pin "U18") (pinfunction "VCCO_33_U18") (pintype "passive"))
      (node (ref "U1") (pin "U8") (pinfunction "VCCO_13_U8") (pintype "passive"))
      (node (ref "U1") (pin "V11") (pinfunction "VCCO_13_V11") (pintype "passive"))
      (node (ref "U1") (pin "V21") (pinfunction "VCCO_33_V21") (pintype "passive"))
      (node (ref "U1") (pin "W14") (pinfunction "VCCO_33_W14") (pintype "passive"))
      (node (ref "U1") (pin "W4") (pinfunction "VCCO_13_W4") (pintype "passive"))
      (node (ref "U1") (pin "Y17") (pinfunction "VCCO_33_Y17") (pintype "passive"))
      (node (ref "U1") (pin "Y7") (pinfunction "VCCO_13_Y7") (pintype "passive"))
    )
  )
)
